# H_bridge.net
KiCad netlist of a schematic drawn in Altium Designer
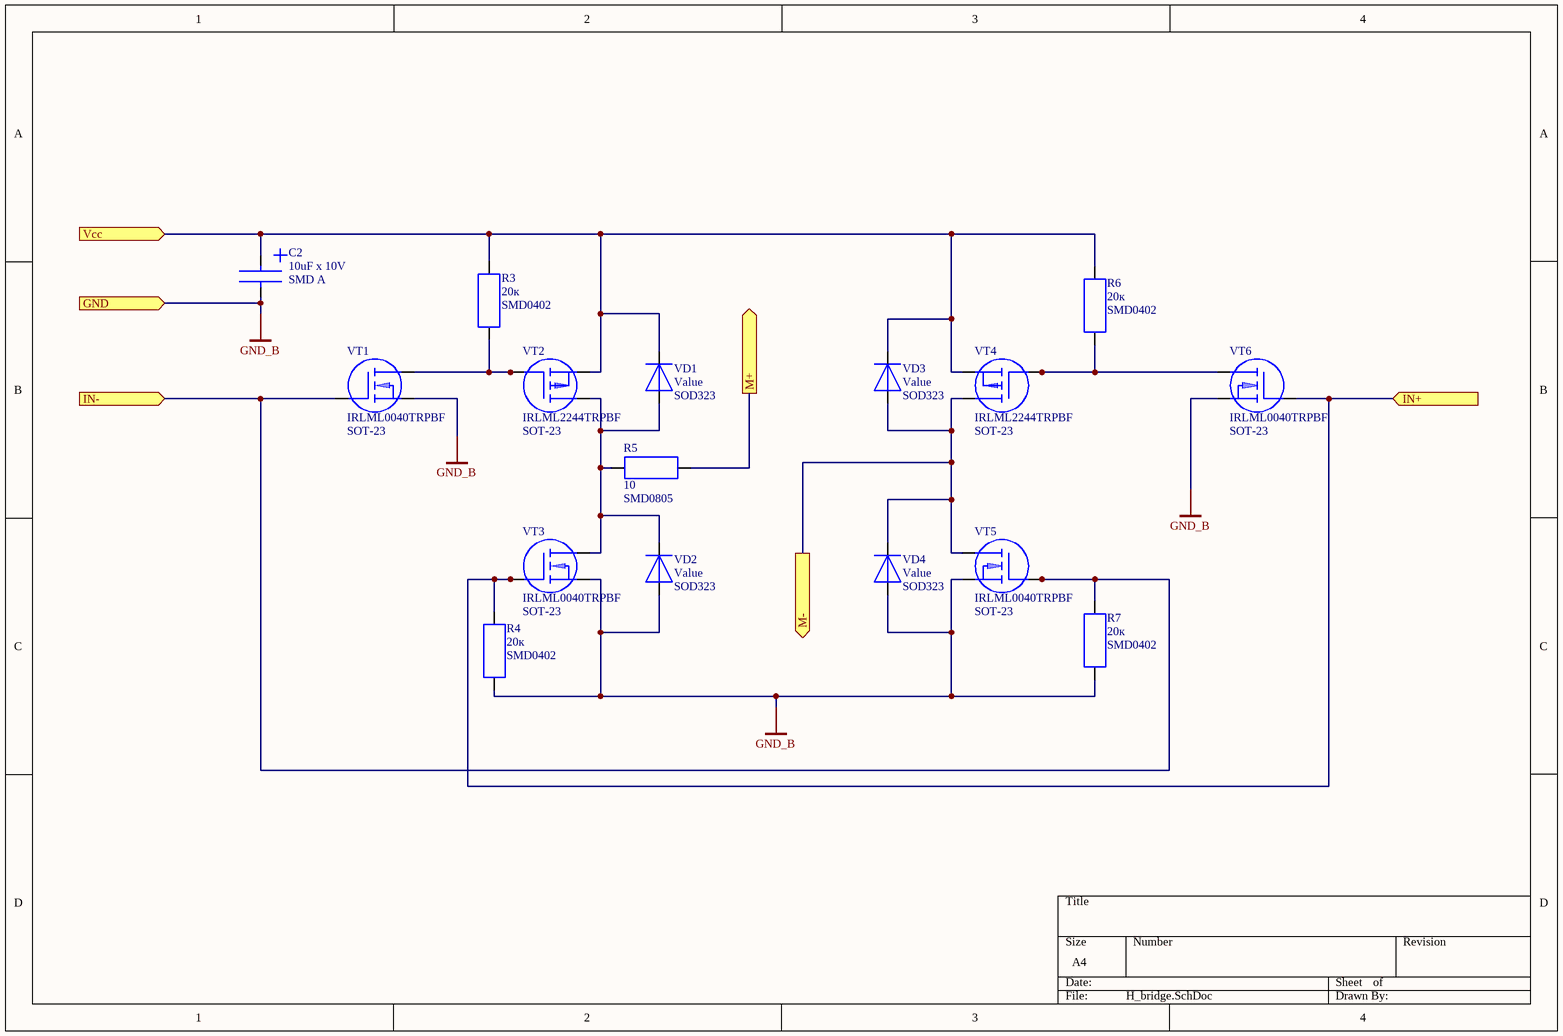
[diagram p0: H_bridge.SchDoc]

(export (version "E")
  (design (tool "Eeschema 10.0.6"))
  (components
    (comp (ref "C2")
      (value "10uF x 10V")
      (footprint "TANT_CAP_A(3216)")
      (fields (field (name "PACKAGE") "SMD A"))
      (libsource (lib "MechanikLibrary") (part "C_TANT_A"))
    )
    (comp (ref "R3")
      (value "20к")
      (footprint "SMD0402(1608)")
      (fields (field (name "PACKAGE") "SMD0402"))
      (libsource (lib "MechanikLibrary") (part "R_0402"))
    )
    (comp (ref "R4")
      (value "20к")
      (footprint "SMD0402(1608)")
      (fields (field (name "PACKAGE") "SMD0402"))
      (libsource (lib "MechanikLibrary") (part "R_0402"))
    )
    (comp (ref "R5")
      (value "10")
      (footprint "SMD0805(2012)")
      (fields (field (name "PACKAGE") "SMD0805"))
      (libsource (lib "MechanikLibrary") (part "R_0805"))
    )
    (comp (ref "R6")
      (value "20к")
      (footprint "SMD0402(1608)")
      (fields (field (name "PACKAGE") "SMD0402"))
      (libsource (lib "MechanikLibrary") (part "R_0402"))
    )
    (comp (ref "R7")
      (value "20к")
      (footprint "SMD0402(1608)")
      (fields (field (name "PACKAGE") "SMD0402"))
      (libsource (lib "MechanikLibrary") (part "R_0402"))
    )
    (comp (ref "VD1")
      (value "Value")
      (footprint "SOD323")
      (fields (field (name "PACKAGE") "SOD323"))
      (libsource (lib "MechanikLibrary") (part "DIODE_SOD323"))
    )
    (comp (ref "VD2")
      (value "Value")
      (footprint "SOD323")
      (fields (field (name "PACKAGE") "SOD323"))
      (libsource (lib "MechanikLibrary") (part "DIODE_SOD323"))
    )
    (comp (ref "VD3")
      (value "Value")
      (footprint "SOD323")
      (fields (field (name "PACKAGE") "SOD323"))
      (libsource (lib "MechanikLibrary") (part "DIODE_SOD323"))
    )
    (comp (ref "VD4")
      (value "Value")
      (footprint "SOD323")
      (fields (field (name "PACKAGE") "SOD323"))
      (libsource (lib "MechanikLibrary") (part "DIODE_SOD323"))
    )
    (comp (ref "VT1")
      (value "IRLML0040TRPBF")
      (footprint "SOT23-3")
      (fields (field (name "PACKAGE") "SOT-23"))
      (libsource (lib "MechanikLibrary") (part "VT_N_MOSFET_SOT23_3"))
    )
    (comp (ref "VT2")
      (value "IRLML2244TRPBF")
      (footprint "SOT23-3")
      (fields (field (name "PACKAGE") "SOT-23"))
      (libsource (lib "MechanikLibrary") (part "VT_P_MOSFET_SOT23_3"))
    )
    (comp (ref "VT3")
      (value "IRLML0040TRPBF")
      (footprint "SOT23-3")
      (fields (field (name "PACKAGE") "SOT-23"))
      (libsource (lib "MechanikLibrary") (part "VT_N_MOSFET_SOT23_3"))
    )
    (comp (ref "VT4")
      (value "IRLML2244TRPBF")
      (footprint "SOT23-3")
      (fields (field (name "PACKAGE") "SOT-23"))
      (libsource (lib "MechanikLibrary") (part "VT_P_MOSFET_SOT23_3"))
    )
    (comp (ref "VT5")
      (value "IRLML0040TRPBF")
      (footprint "SOT23-3")
      (fields (field (name "PACKAGE") "SOT-23"))
      (libsource (lib "MechanikLibrary") (part "VT_N_MOSFET_SOT23_3"))
    )
    (comp (ref "VT6")
      (value "IRLML0040TRPBF")
      (footprint "SOT23-3")
      (fields (field (name "PACKAGE") "SOT-23"))
      (libsource (lib "MechanikLibrary") (part "VT_N_MOSFET_SOT23_3"))
    )
  )
  (nets
    (net (code "1") (name "/IN+") (class "Default")
      (node (ref "R4") (pin "1") (pintype "passive"))
      (node (ref "VT3") (pin "1") (pintype "passive"))
      (node (ref "VT6") (pin "1") (pintype "passive"))
    )
    (net (code "2") (name "/IN-") (class "Default")
      (node (ref "R7") (pin "1") (pintype "passive"))
      (node (ref "VT1") (pin "1") (pintype "passive"))
      (node (ref "VT5") (pin "1") (pintype "passive"))
    )
    (net (code "3") (name "/M+") (class "Default") (node (ref "R5") (pin "1") (pintype "passive")))
    (net (code "4") (name "/M-") (class "Default")
      (node (ref "VD3") (pin "1") (pintype "passive"))
      (node (ref "VD4") (pin "2") (pintype "passive"))
      (node (ref "VT4") (pin "3") (pintype "passive"))
      (node (ref "VT5") (pin "3") (pintype "passive"))
    )
    (net (code "5") (name "/Vcc") (class "Default")
      (node (ref "C2") (pin "1") (pintype "passive"))
      (node (ref "R3") (pin "1") (pintype "passive"))
      (node (ref "R6") (pin "1") (pintype "passive"))
      (node (ref "VD1") (pin "2") (pintype "passive"))
      (node (ref "VD3") (pin "2") (pintype "passive"))
      (node (ref "VT2") (pin "2") (pintype "passive"))
      (node (ref "VT4") (pin "2") (pintype "passive"))
    )
    (net (code "6") (name "GND_B") (class "Default")
      (node (ref "C2") (pin "2") (pintype "passive"))
      (node (ref "R4") (pin "2") (pintype "passive"))
      (node (ref "R7") (pin "2") (pintype "passive"))
      (node (ref "VD2") (pin "1") (pintype "passive"))
      (node (ref "VD4") (pin "1") (pintype "passive"))
      (node (ref "VT1") (pin "2") (pintype "passive"))
      (node (ref "VT3") (pin "2") (pintype "passive"))
      (node (ref "VT5") (pin "2") (pintype "passive"))
      (node (ref "VT6") (pin "2") (pintype "passive"))
    )
    (net (code "7") (name "Net-(R3-Pad2)") (class "Default")
      (node (ref "R3") (pin "2") (pintype "passive"))
      (node (ref "VT1") (pin "3") (pintype "passive"))
      (node (ref "VT2") (pin "1") (pintype "passive"))
    )
    (net (code "8") (name "Net-(R5-Pad2)") (class "Default")
      (node (ref "R5") (pin "2") (pintype "passive"))
      (node (ref "VD1") (pin "1") (pintype "passive"))
      (node (ref "VD2") (pin "2") (pintype "passive"))
      (node (ref "VT2") (pin "3") (pintype "passive"))
      (node (ref "VT3") (pin "3") (pintype "passive"))
    )
    (net (code "9") (name "Net-(R6-Pad2)") (class "Default")
      (node (ref "R6") (pin "2") (pintype "passive"))
      (node (ref "VT4") (pin "1") (pintype "passive"))
      (node (ref "VT6") (pin "3") (pintype "passive"))
    )
  )
)
